# DDS.net
KiCad netlist of a schematic drawn in Altium Designer
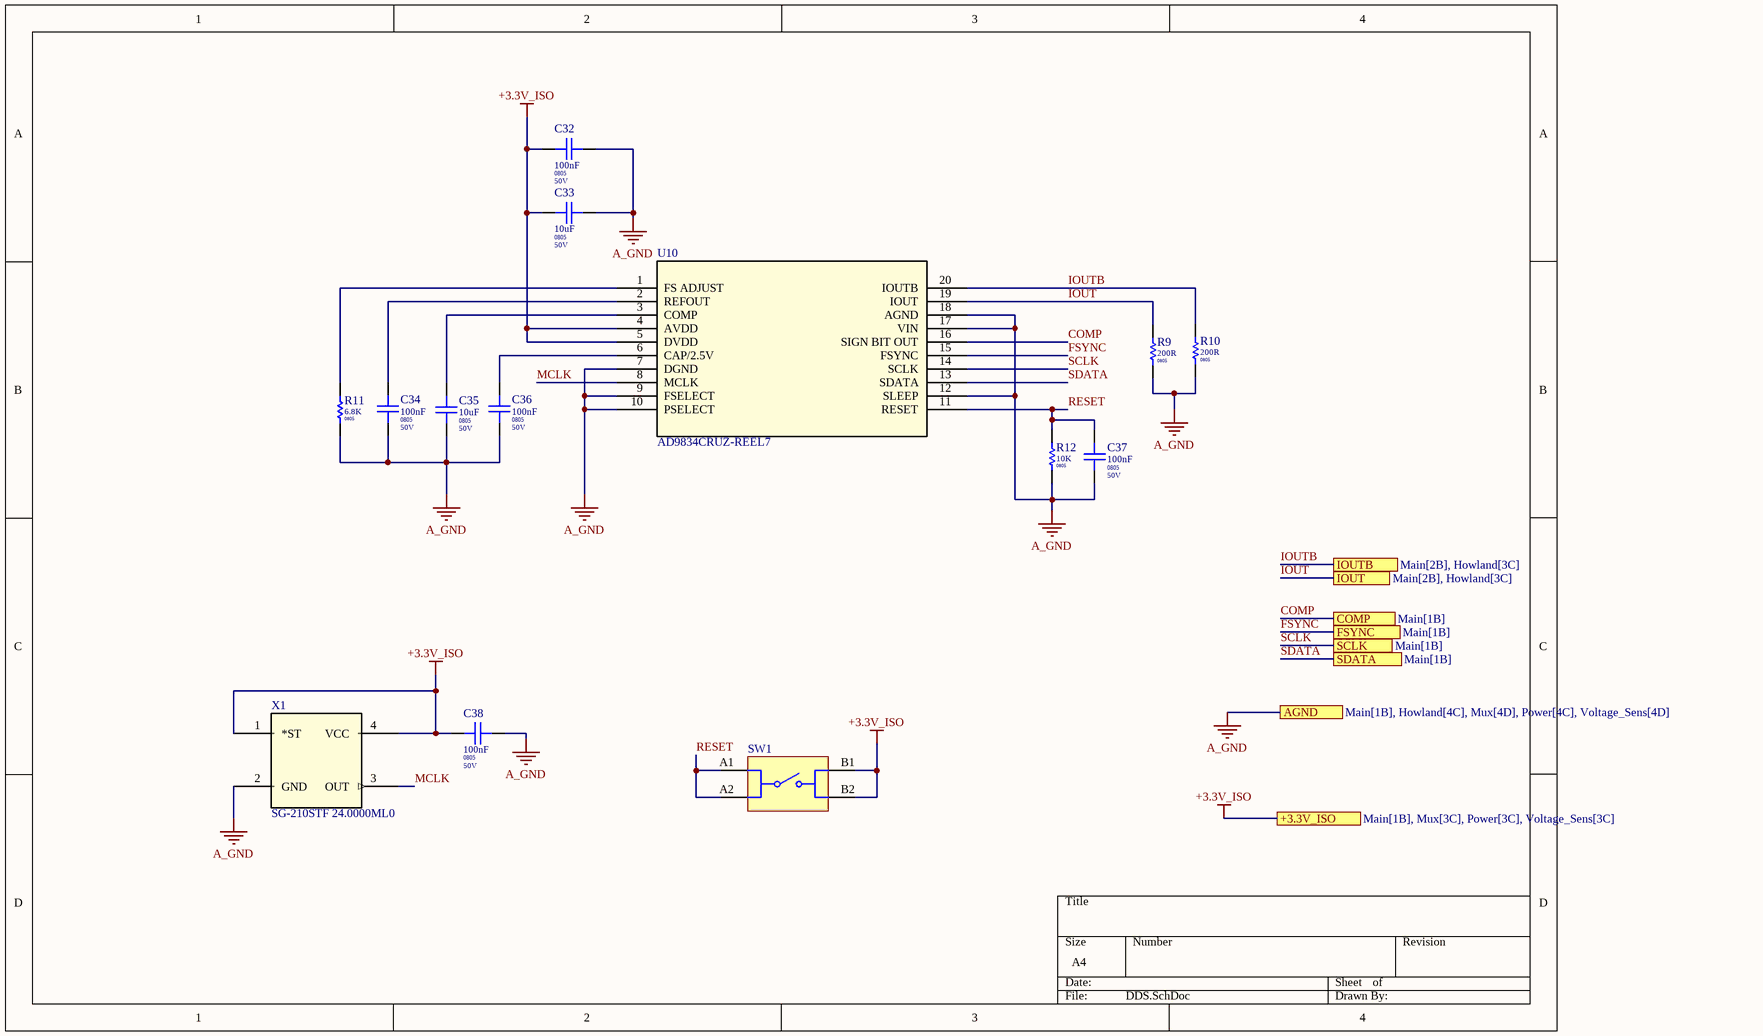
[diagram p0: DDS.SchDoc]

(export (version "E")
  (design (tool "Eeschema 10.0.6"))
  (components
    (comp (ref "C32")
      (value "100nF")
      (footprint "CAPC 0805")
      (description "Capacitor Ceramic 100nF 50V 0805")
      (fields
        (field (name "TOLERANCE") "%10")
        (field (name "PACKAGE / CASE") "0805")
        (field (name "VOLTAGE") "50V")
        (field (name "PART NUMBER") "CAPC0572")
      )
      (libsource (lib "Aesk Database Library") (part "NPCapacitor"))
    )
    (comp (ref "C33")
      (value "10uF")
      (footprint "CAPC 0805")
      (description "Capacitor Ceramic 10uF 50V 0805")
      (fields
        (field (name "TOLERANCE") "%10")
        (field (name "PACKAGE / CASE") "0805")
        (field (name "VOLTAGE") "50V")
        (field (name "PART NUMBER") "CAPC0588")
      )
      (libsource (lib "Aesk Database Library") (part "NPCapacitor"))
    )
    (comp (ref "C34")
      (value "100nF")
      (footprint "CAPC 0805")
      (description "Capacitor Ceramic 100nF 50V 0805")
      (fields
        (field (name "TOLERANCE") "%10")
        (field (name "PACKAGE / CASE") "0805")
        (field (name "VOLTAGE") "50V")
        (field (name "PART NUMBER") "CAPC0572")
      )
      (libsource (lib "Aesk Database Library") (part "NPCapacitor"))
    )
    (comp (ref "C35")
      (value "10uF")
      (footprint "CAPC 0805")
      (description "Capacitor Ceramic 10uF 50V 0805")
      (fields
        (field (name "TOLERANCE") "%10")
        (field (name "PACKAGE / CASE") "0805")
        (field (name "VOLTAGE") "50V")
        (field (name "PART NUMBER") "CAPC0588")
      )
      (libsource (lib "Aesk Database Library") (part "NPCapacitor"))
    )
    (comp (ref "C36")
      (value "100nF")
      (footprint "CAPC 0805")
      (description "Capacitor Ceramic 100nF 50V 0805")
      (fields
        (field (name "TOLERANCE") "%10")
        (field (name "PACKAGE / CASE") "0805")
        (field (name "VOLTAGE") "50V")
        (field (name "PART NUMBER") "CAPC0572")
      )
      (libsource (lib "Aesk Database Library") (part "NPCapacitor"))
    )
    (comp (ref "C37")
      (value "100nF")
      (footprint "CAPC 0805")
      (description "Capacitor Ceramic 100nF 50V 0805")
      (fields
        (field (name "TOLERANCE") "%10")
        (field (name "PACKAGE / CASE") "0805")
        (field (name "VOLTAGE") "50V")
        (field (name "PART NUMBER") "CAPC0572")
      )
      (libsource (lib "Aesk Database Library") (part "NPCapacitor"))
    )
    (comp (ref "C38")
      (value "100nF")
      (footprint "CAPC 0805")
      (description "Capacitor Ceramic 100nF 50V 0805")
      (fields
        (field (name "TOLERANCE") "%10")
        (field (name "PACKAGE / CASE") "0805")
        (field (name "VOLTAGE") "50V")
        (field (name "PART NUMBER") "CAPC0572")
      )
      (libsource (lib "Aesk Database Library") (part "NPCapacitor"))
    )
    (comp (ref "R9")
      (value "200R")
      (footprint "RESC 0805")
      (description "200R 0805")
      (fields
        (field (name "TOLERANCE") "%5")
        (field (name "POWER") "1/10W")
        (field (name "PACKAGE / CASE") "0805")
      )
      (libsource (lib "Aesk Database Library") (part "Resistor"))
    )
    (comp (ref "R10")
      (value "200R")
      (footprint "RESC 0805")
      (description "200R 0805")
      (fields
        (field (name "TOLERANCE") "%5")
        (field (name "POWER") "1/10W")
        (field (name "PACKAGE / CASE") "0805")
      )
      (libsource (lib "Aesk Database Library") (part "Resistor"))
    )
    (comp (ref "R11")
      (value "6.8K")
      (footprint "RESC 0805")
      (description "6.8K 0805")
      (fields
        (field (name "TOLERANCE") "%5")
        (field (name "POWER") "1/10W")
        (field (name "PACKAGE / CASE") "0805")
      )
      (libsource (lib "Aesk Database Library") (part "Resistor"))
    )
    (comp (ref "R12")
      (value "10K")
      (footprint "RESC 0805")
      (description "10K 0805")
      (fields
        (field (name "TOLERANCE") "%5")
        (field (name "POWER") "1/10W")
        (field (name "PACKAGE / CASE") "0805")
      )
      (libsource (lib "Aesk Database Library") (part "Resistor"))
    )
    (comp (ref "SW1")
      (value "430451025836")
      (footprint "430451025836")
      (description "WS-TASV SMT Washable Tact Switch, 6mm x 6mm x 2.5mm, SPST-NO, 360gf, 12V, 50mA")
      (fields (field (name "MANUFACTURER") "Wurth Elektronik"))
      (libsource (lib "WE - Electromechanical Components") (part "SPST-NO_4P"))
    )
    (comp (ref "U10")
      (value "AD9834CRUZ-REEL7")
      (footprint "RU_20_ADI-M")
      (description "20 mW Power, 2.3 V to 5.5 V, 75 MHz Complete DDS")
      (fields (field (name "COPYRIGHT") "Copyright (C) 2026 Ultra Librarian. All rights reserved."))
      (libsource (lib "Schlib1") (part "AD9834CRUZ-REEL7"))
    )
    (comp (ref "X1")
      (value "SG-210STF 24.0000ML0")
      (footprint "SG-210STF_EPS")
      (description "Description")
      (fields (field (name "COPYRIGHT") "Copyright (C) 2025 Ultra Librarian. All rights reserved."))
      (libsource (lib "Schlib1") (part "SG-210STF 24.0000ML0"))
    )
  )
  (nets
    (net (code "1") (name "+3.3V_ISO") (class "Default")
      (node (ref "C32") (pin "2") (pinfunction "2_2") (pintype "passive"))
      (node (ref "C33") (pin "2") (pinfunction "2_2") (pintype "passive"))
      (node (ref "C38") (pin "2") (pinfunction "2_2") (pintype "passive"))
      (node (ref "SW1") (pin "B1") (pinfunction "B1_B1") (pintype "passive"))
      (node (ref "SW1") (pin "B2") (pinfunction "B2_B2") (pintype "passive"))
      (node (ref "U10") (pin "4") (pinfunction "AVDD_4") (pintype "power_in"))
      (node (ref "U10") (pin "5") (pinfunction "DVDD_5") (pintype "power_in"))
      (node (ref "X1") (pin "1") (pinfunction "*ST_1") (pintype "passive"))
      (node (ref "X1") (pin "4") (pinfunction "VCC_4") (pintype "power_in"))
    )
    (net (code "2") (name "/COMP") (class "Default")
      (node (ref "U10") (pin "16") (pinfunction "SIGN_BIT_OUT_16") (pintype "passive"))
    )
    (net (code "3") (name "/FSYNC") (class "Default")
      (node (ref "U10") (pin "15") (pinfunction "FSYNC_15") (pintype "passive"))
    )
    (net (code "4") (name "/IOUT") (class "Default")
      (node (ref "R9") (pin "2") (pinfunction "2_2") (pintype "passive"))
      (node (ref "U10") (pin "19") (pinfunction "IOUT_19") (pintype "passive"))
    )
    (net (code "5") (name "/IOUTB") (class "Default")
      (node (ref "R10") (pin "2") (pinfunction "2_2") (pintype "passive"))
      (node (ref "U10") (pin "20") (pinfunction "IOUTB_20") (pintype "passive"))
    )
    (net (code "6") (name "/MCLK") (class "Default")
      (node (ref "U10") (pin "8") (pinfunction "MCLK_8") (pintype "passive"))
      (node (ref "X1") (pin "3") (pinfunction "OUT_3") (pintype "output"))
    )
    (net (code "7") (name "/RESET") (class "Default")
      (node (ref "C37") (pin "1") (pinfunction "1_1") (pintype "passive"))
      (node (ref "R12") (pin "2") (pinfunction "2_2") (pintype "passive"))
      (node (ref "SW1") (pin "A1") (pinfunction "A1_A1") (pintype "passive"))
      (node (ref "SW1") (pin "A2") (pinfunction "A2_A2") (pintype "passive"))
      (node (ref "U10") (pin "11") (pinfunction "RESET_11") (pintype "passive"))
    )
    (net (code "8") (name "/SCLK") (class "Default")
      (node (ref "U10") (pin "14") (pinfunction "SCLK_14") (pintype "passive"))
    )
    (net (code "9") (name "/SDATA") (class "Default")
      (node (ref "U10") (pin "13") (pinfunction "SDATA_13") (pintype "passive"))
    )
    (net (code "10") (name "A_GND") (class "Default")
      (node (ref "C32") (pin "1") (pinfunction "1_1") (pintype "passive"))
      (node (ref "C33") (pin "1") (pinfunction "1_1") (pintype "passive"))
      (node (ref "C34") (pin "2") (pinfunction "2_2") (pintype "passive"))
      (node (ref "C35") (pin "2") (pinfunction "2_2") (pintype "passive"))
      (node (ref "C36") (pin "2") (pinfunction "2_2") (pintype "passive"))
      (node (ref "C37") (pin "2") (pinfunction "2_2") (pintype "passive"))
      (node (ref "C38") (pin "1") (pinfunction "1_1") (pintype "passive"))
      (node (ref "R10") (pin "1") (pinfunction "1_1") (pintype "passive"))
      (node (ref "R11") (pin "1") (pinfunction "1_1") (pintype "passive"))
      (node (ref "R12") (pin "1") (pinfunction "1_1") (pintype "passive"))
      (node (ref "R9") (pin "1") (pinfunction "1_1") (pintype "passive"))
      (node (ref "U10") (pin "10") (pinfunction "PSELECT_10") (pintype "passive"))
      (node (ref "U10") (pin "12") (pinfunction "SLEEP_12") (pintype "passive"))
      (node (ref "U10") (pin "17") (pinfunction "VIN_17") (pintype "passive"))
      (node (ref "U10") (pin "18") (pinfunction "AGND_18") (pintype "passive"))
      (node (ref "U10") (pin "7") (pinfunction "DGND_7") (pintype "passive"))
      (node (ref "U10") (pin "9") (pinfunction "FSELECT_9") (pintype "passive"))
      (node (ref "X1") (pin "2") (pinfunction "GND_2") (pintype "power_in"))
    )
    (net (code "11") (name "Net-(U10-CAP{slash}2.5V)") (class "Default")
      (node (ref "C36") (pin "1") (pinfunction "1_1") (pintype "passive"))
      (node (ref "U10") (pin "6") (pinfunction "CAP/2.5V_6") (pintype "passive"))
    )
    (net (code "12") (name "Net-(U10-COMP)") (class "Default")
      (node (ref "C35") (pin "1") (pinfunction "1_1") (pintype "passive"))
      (node (ref "U10") (pin "3") (pinfunction "COMP_3") (pintype "passive"))
    )
    (net (code "13") (name "Net-(U10-FS_ADJUST)") (class "Default")
      (node (ref "R11") (pin "2") (pinfunction "2_2") (pintype "passive"))
      (node (ref "U10") (pin "1") (pinfunction "FS_ADJUST_1") (pintype "passive"))
    )
    (net (code "14") (name "Net-(U10-REFOUT)") (class "Default")
      (node (ref "C34") (pin "1") (pinfunction "1_1") (pintype "passive"))
      (node (ref "U10") (pin "2") (pinfunction "REFOUT_2") (pintype "passive"))
    )
  )
)
